# Microcontroller.net
KiCad netlist of a schematic drawn in Altium Designer
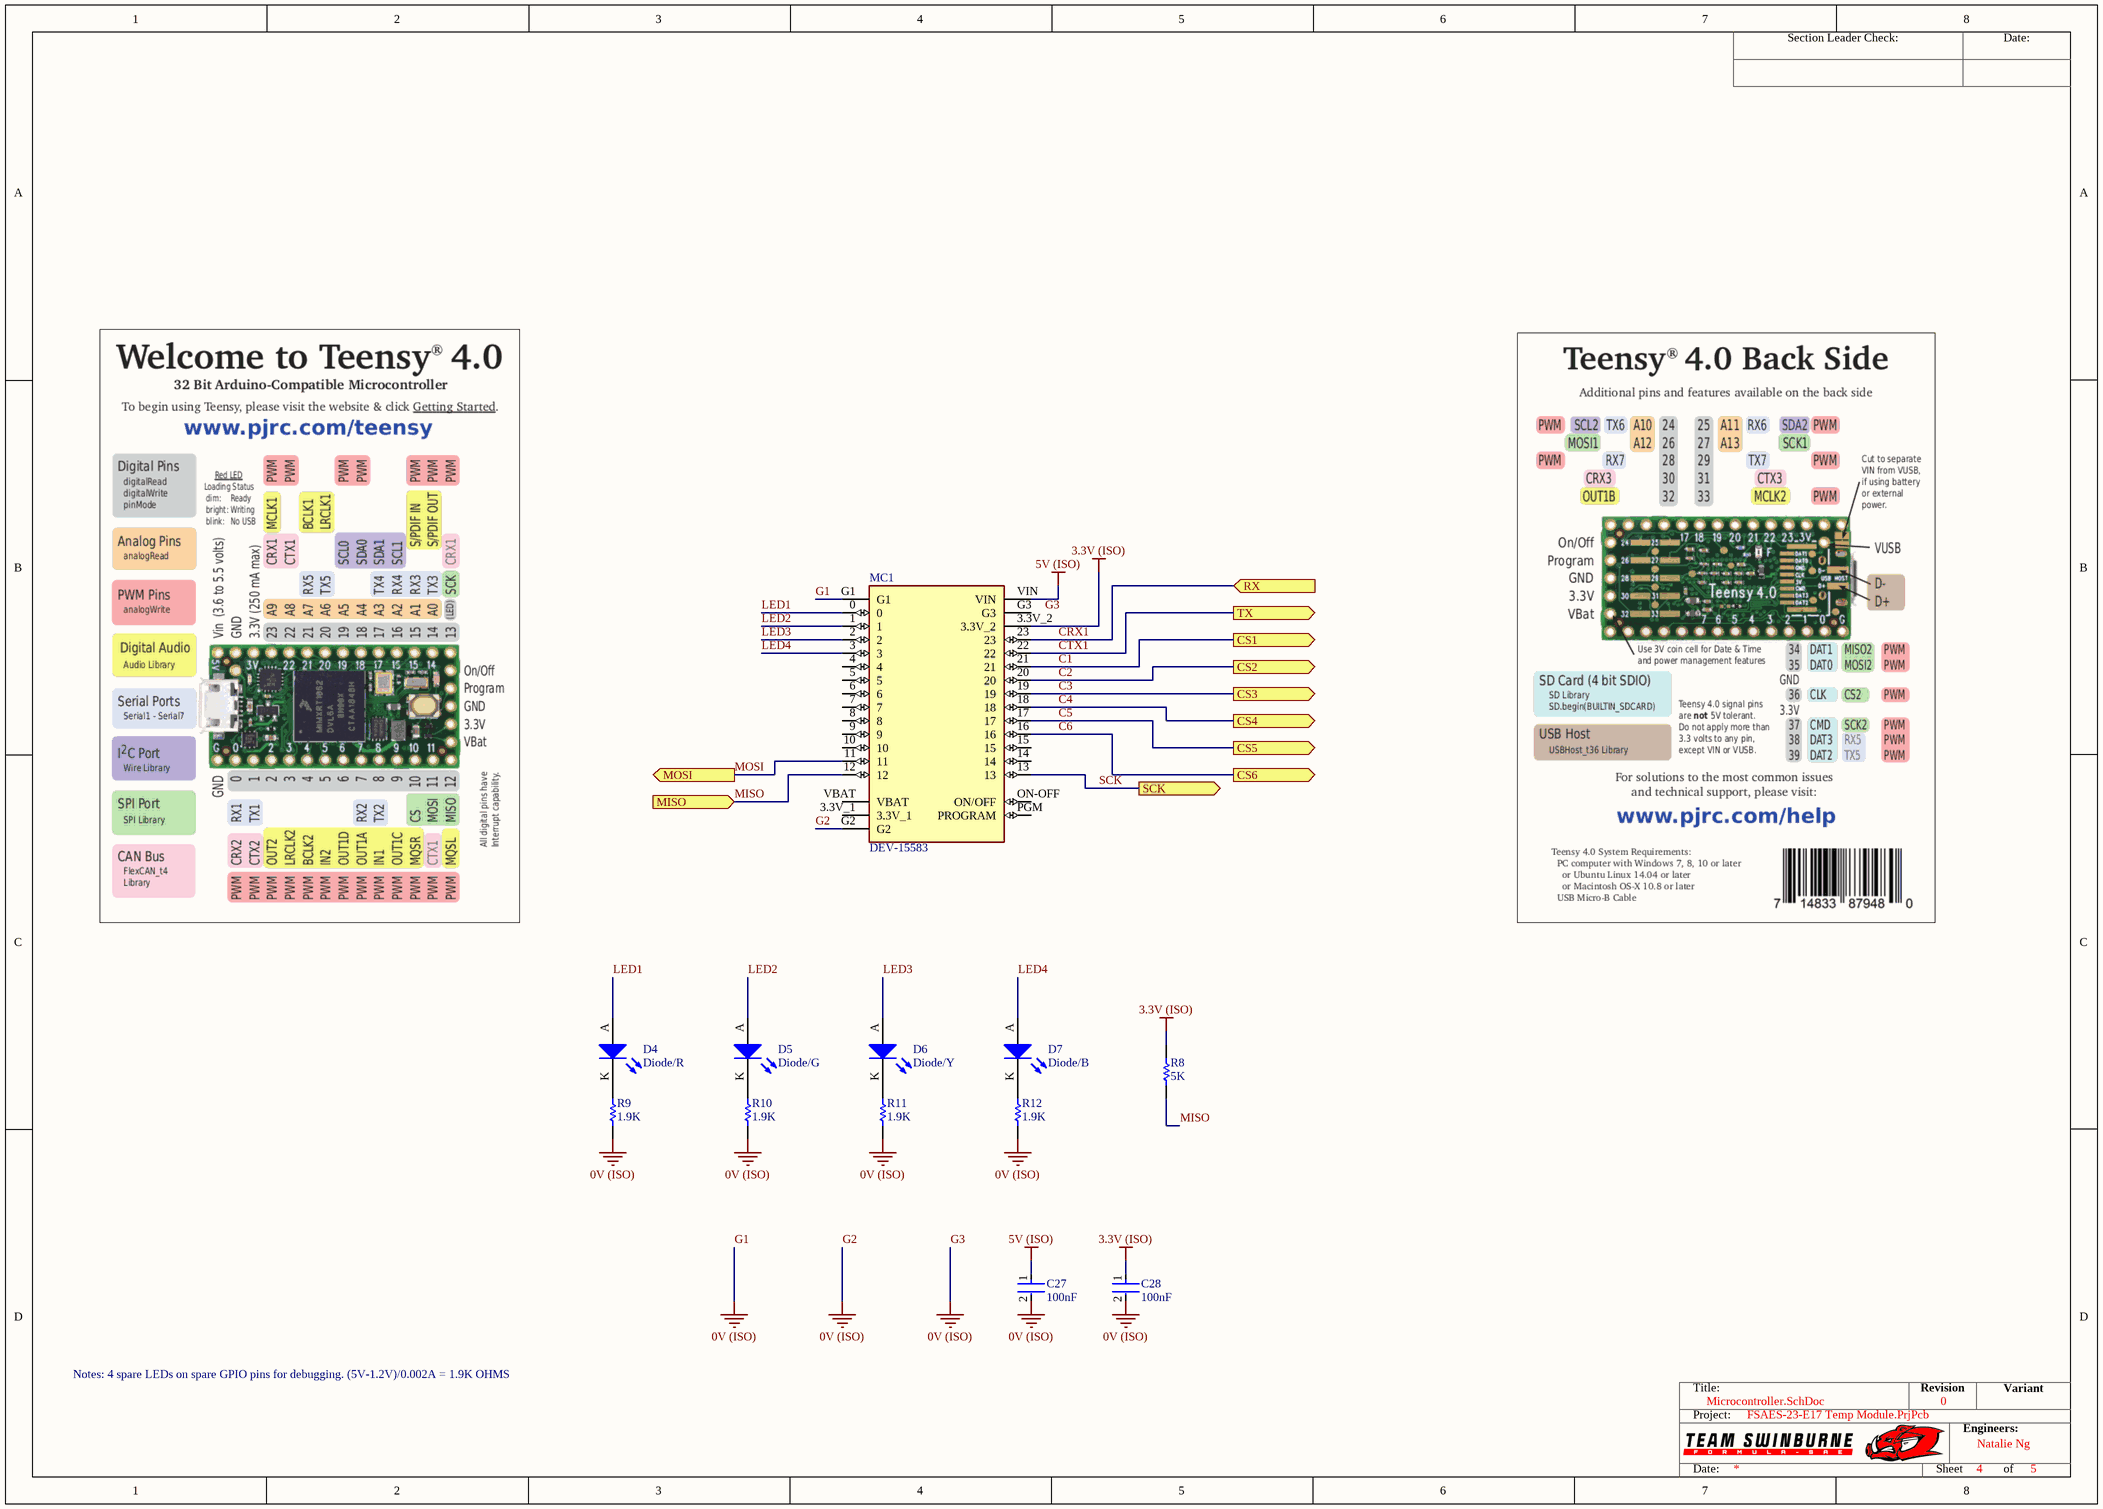
[diagram p0: Microcontroller.SchDoc]

(export (version "E")
  (design (tool "Eeschema 10.0.6"))
  (components
    (comp (ref "C27")
      (value "100nF")
      (footprint "FP-GCM319-0_15-IPC_A")
      (description "CAP CER 10000PF 100V NP0 1206")
      (fields (field (name "TOLERANCE") "5%"))
      (libsource (lib "Team Swinburne") (part "b4654b650e69147ec39a6b967a45e02"))
    )
    (comp (ref "C28")
      (value "100nF")
      (footprint "FP-GCM319-0_15-IPC_A")
      (description "CAP CER 10000PF 100V NP0 1206")
      (fields (field (name "TOLERANCE") "5%"))
      (libsource (lib "Team Swinburne") (part "b4654b650e69147ec39a6b967a45e02"))
    )
    (comp (ref "D4")
      (value "Diode/R")
      (footprint "0805 LED")
      (description "Red LED Indication - Discrete 1.75V 0805 (2012 Metric)")
      (fields (field (name "PART NUMBER") "SML-210LTT86"))
      (libsource (lib "Team Swinburne") (part "LED"))
    )
    (comp (ref "D5")
      (value "Diode/G")
      (footprint "0805 LED")
      (description "Green LED Indication - Discrete 1.75V 0805 (2012 Metric)")
      (fields (field (name "PART NUMBER") "SML-210FTT86"))
      (libsource (lib "Team Swinburne") (part "LED"))
    )
    (comp (ref "D6")
      (value "Diode/Y")
      (footprint "0805 LED")
      (description "Yellow LED Indication - Discrete 1.75V 0805 (2012 Metric)")
      (fields (field (name "PART NUMBER") "SML-211YTT86"))
      (libsource (lib "Team Swinburne") (part "LED"))
    )
    (comp (ref "D7")
      (value "Diode/B")
      (footprint "0805 LED")
      (description "LED BLUE CLEAR 2012 SMD")
      (fields (field (name "PART NUMBER") "SML-MN2BCTT86C"))
      (libsource (lib "Team Swinburne") (part "LED"))
    )
    (comp (ref "MC1")
      (value "DEV-15583")
      (footprint "DEV-15583-Footprint-1")
      (description "Teensy 4.0 Microcontroller Board")
      (libsource (lib "Team Swinburne") (part "Teensy 4.0-Symbol-1"))
    )
    (comp (ref "R8")
      (value "5K")
      (footprint "Y16295K00000T9R-Footprint-1")
      (description "RED SMD 5K OHM 1/10W 0805")
      (libsource (lib "Team Swinburne") (part "Y16295K00000T9R-Symbol-1"))
    )
    (comp (ref "R9")
      (value "1.9K")
      (footprint "Y16241K90000T9R-Footprint-1")
      (description "RES SMD 1.9K OHM 1/5W 0805")
      (fields (field (name "TOLERANCE") "0.01%"))
      (libsource (lib "Team Swinburne") (part "Y16241K90000T9R-Symbol-1"))
    )
    (comp (ref "R10")
      (value "1.9K")
      (footprint "Y16241K90000T9R-Footprint-1")
      (description "RES SMD 1.9K OHM 1/5W 0805")
      (fields (field (name "TOLERANCE") "0.01%"))
      (libsource (lib "Team Swinburne") (part "Y16241K90000T9R-Symbol-1"))
    )
    (comp (ref "R11")
      (value "1.9K")
      (footprint "Y16241K90000T9R-Footprint-1")
      (description "RES SMD 1.9K OHM 1/5W 0805")
      (fields (field (name "TOLERANCE") "0.01%"))
      (libsource (lib "Team Swinburne") (part "Y16241K90000T9R-Symbol-1"))
    )
    (comp (ref "R12")
      (value "1.9K")
      (footprint "Y16241K90000T9R-Footprint-1")
      (description "RES SMD 1.9K OHM 1/5W 0805")
      (fields (field (name "TOLERANCE") "0.01%"))
      (libsource (lib "Team Swinburne") (part "Y16241K90000T9R-Symbol-1"))
    )
  )
  (nets
    (net (code "1") (name "/C1") (class "Default")
      (node (ref "MC1") (pin "21") (pinfunction "21_21") (pintype "bidirectional"))
    )
    (net (code "2") (name "/C2") (class "Default")
      (node (ref "MC1") (pin "20") (pinfunction "20_20") (pintype "bidirectional"))
    )
    (net (code "3") (name "/C3") (class "Default")
      (node (ref "MC1") (pin "19") (pinfunction "19_19") (pintype "bidirectional"))
    )
    (net (code "4") (name "/C4") (class "Default")
      (node (ref "MC1") (pin "18") (pinfunction "18_18") (pintype "bidirectional"))
    )
    (net (code "5") (name "/C5") (class "Default")
      (node (ref "MC1") (pin "17") (pinfunction "17_17") (pintype "bidirectional"))
    )
    (net (code "6") (name "/C6") (class "Default")
      (node (ref "MC1") (pin "16") (pinfunction "16_16") (pintype "bidirectional"))
    )
    (net (code "7") (name "/CRX1") (class "Default")
      (node (ref "MC1") (pin "23") (pinfunction "23_23") (pintype "bidirectional"))
    )
    (net (code "8") (name "/CTX1") (class "Default")
      (node (ref "MC1") (pin "22") (pinfunction "22_22") (pintype "bidirectional"))
    )
    (net (code "9") (name "/LED1") (class "Default")
      (node (ref "D4") (pin "A") (pinfunction "A_A") (pintype "passive"))
      (node (ref "MC1") (pin "0") (pinfunction "0_0") (pintype "bidirectional"))
    )
    (net (code "10") (name "/LED2") (class "Default")
      (node (ref "D5") (pin "A") (pinfunction "A_A") (pintype "passive"))
      (node (ref "MC1") (pin "1") (pinfunction "1_1") (pintype "bidirectional"))
    )
    (net (code "11") (name "/LED3") (class "Default")
      (node (ref "D6") (pin "A") (pinfunction "A_A") (pintype "passive"))
      (node (ref "MC1") (pin "2") (pinfunction "2_2") (pintype "bidirectional"))
    )
    (net (code "12") (name "/LED4") (class "Default")
      (node (ref "D7") (pin "A") (pinfunction "A_A") (pintype "passive"))
      (node (ref "MC1") (pin "3") (pinfunction "3_3") (pintype "bidirectional"))
    )
    (net (code "13") (name "/MISO") (class "Default")
      (node (ref "MC1") (pin "12") (pinfunction "12_12") (pintype "bidirectional"))
      (node (ref "R8") (pin "1") (pinfunction "1_1") (pintype "passive"))
    )
    (net (code "14") (name "/MOSI") (class "Default")
      (node (ref "MC1") (pin "11") (pinfunction "11_11") (pintype "bidirectional"))
    )
    (net (code "15") (name "/SCK") (class "Default")
      (node (ref "MC1") (pin "13") (pinfunction "13_13") (pintype "bidirectional"))
    )
    (net (code "16") (name "0V (ISO)") (class "Default")
      (node (ref "C27") (pin "2") (pinfunction "2_2") (pintype "passive"))
      (node (ref "C28") (pin "2") (pinfunction "2_2") (pintype "passive"))
      (node (ref "MC1") (pin "G1") (pinfunction "G1_G1") (pintype "power_in"))
      (node (ref "MC1") (pin "G2") (pinfunction "G2_G2") (pintype "power_in"))
      (node (ref "R10") (pin "1") (pinfunction "1_1") (pintype "passive"))
      (node (ref "R11") (pin "1") (pinfunction "1_1") (pintype "passive"))
      (node (ref "R12") (pin "1") (pinfunction "1_1") (pintype "passive"))
      (node (ref "R9") (pin "1") (pinfunction "1_1") (pintype "passive"))
    )
    (net (code "17") (name "3.3V (ISO)") (class "Default")
      (node (ref "C28") (pin "1") (pinfunction "1_1") (pintype "passive"))
      (node (ref "MC1") (pin "3.3V_2") (pinfunction "3.3V_2_3.3V_2") (pintype "power_in"))
      (node (ref "R8") (pin "2") (pinfunction "2_2") (pintype "passive"))
    )
    (net (code "18") (name "5V (ISO)") (class "Default")
      (node (ref "C27") (pin "1") (pinfunction "1_1") (pintype "passive"))
      (node (ref "MC1") (pin "VIN") (pinfunction "VIN_VIN") (pintype "power_in"))
    )
    (net (code "19") (name "Net-(D4-PadK)") (class "Default")
      (node (ref "D4") (pin "K") (pinfunction "K_K") (pintype "passive"))
      (node (ref "R9") (pin "2") (pinfunction "2_2") (pintype "passive"))
    )
    (net (code "20") (name "Net-(D5-PadK)") (class "Default")
      (node (ref "D5") (pin "K") (pinfunction "K_K") (pintype "passive"))
      (node (ref "R10") (pin "2") (pinfunction "2_2") (pintype "passive"))
    )
    (net (code "21") (name "Net-(D6-PadK)") (class "Default")
      (node (ref "D6") (pin "K") (pinfunction "K_K") (pintype "passive"))
      (node (ref "R11") (pin "2") (pinfunction "2_2") (pintype "passive"))
    )
    (net (code "22") (name "Net-(D7-PadK)") (class "Default")
      (node (ref "D7") (pin "K") (pinfunction "K_K") (pintype "passive"))
      (node (ref "R12") (pin "2") (pinfunction "2_2") (pintype "passive"))
    )
    (net (code "23") (name "unconnected-(MC1-ON{slash}OFF-PadON-OFF)") (class "Default")
      (node (ref "MC1") (pin "ON-OFF") (pinfunction "ON/OFF_ON-OFF") (pintype "bidirectional"))
    )
    (net (code "24") (name "unconnected-(MC1-PROGRAM-PadPGM)") (class "Default")
      (node (ref "MC1") (pin "PGM") (pinfunction "PROGRAM_PGM") (pintype "bidirectional"))
    )
    (net (code "25") (name "unconnected-(MC1-Pad3.3V_1)") (class "Default")
      (node (ref "MC1") (pin "3.3V_1") (pinfunction "3.3V_1_3.3V_1") (pintype "power_in"))
    )
    (net (code "26") (name "unconnected-(MC1-Pad4)") (class "Default")
      (node (ref "MC1") (pin "4") (pinfunction "4_4") (pintype "bidirectional"))
    )
    (net (code "27") (name "unconnected-(MC1-Pad5)") (class "Default")
      (node (ref "MC1") (pin "5") (pinfunction "5_5") (pintype "bidirectional"))
    )
    (net (code "28") (name "unconnected-(MC1-Pad6)") (class "Default")
      (node (ref "MC1") (pin "6") (pinfunction "6_6") (pintype "bidirectional"))
    )
    (net (code "29") (name "unconnected-(MC1-Pad7)") (class "Default")
      (node (ref "MC1") (pin "7") (pinfunction "7_7") (pintype "bidirectional"))
    )
    (net (code "30") (name "unconnected-(MC1-Pad8)") (class "Default")
      (node (ref "MC1") (pin "8") (pinfunction "8_8") (pintype "bidirectional"))
    )
    (net (code "31") (name "unconnected-(MC1-Pad9)") (class "Default")
      (node (ref "MC1") (pin "9") (pinfunction "9_9") (pintype "bidirectional"))
    )
    (net (code "32") (name "unconnected-(MC1-Pad10)") (class "Default")
      (node (ref "MC1") (pin "10") (pinfunction "10_10") (pintype "bidirectional"))
    )
    (net (code "33") (name "unconnected-(MC1-Pad14)") (class "Default")
      (node (ref "MC1") (pin "14") (pinfunction "14_14") (pintype "bidirectional"))
    )
    (net (code "34") (name "unconnected-(MC1-Pad15)") (class "Default")
      (node (ref "MC1") (pin "15") (pinfunction "15_15") (pintype "bidirectional"))
    )
    (net (code "35") (name "unconnected-(MC1-PadG3)") (class "Default")
      (node (ref "MC1") (pin "G3") (pinfunction "G3_G3") (pintype "power_in"))
    )
    (net (code "36") (name "unconnected-(MC1-PadVBAT)") (class "Default")
      (node (ref "MC1") (pin "VBAT") (pinfunction "VBAT_VBAT") (pintype "power_in"))
    )
  )
)
